# display.net
KiCad netlist of a schematic drawn in Altium Designer
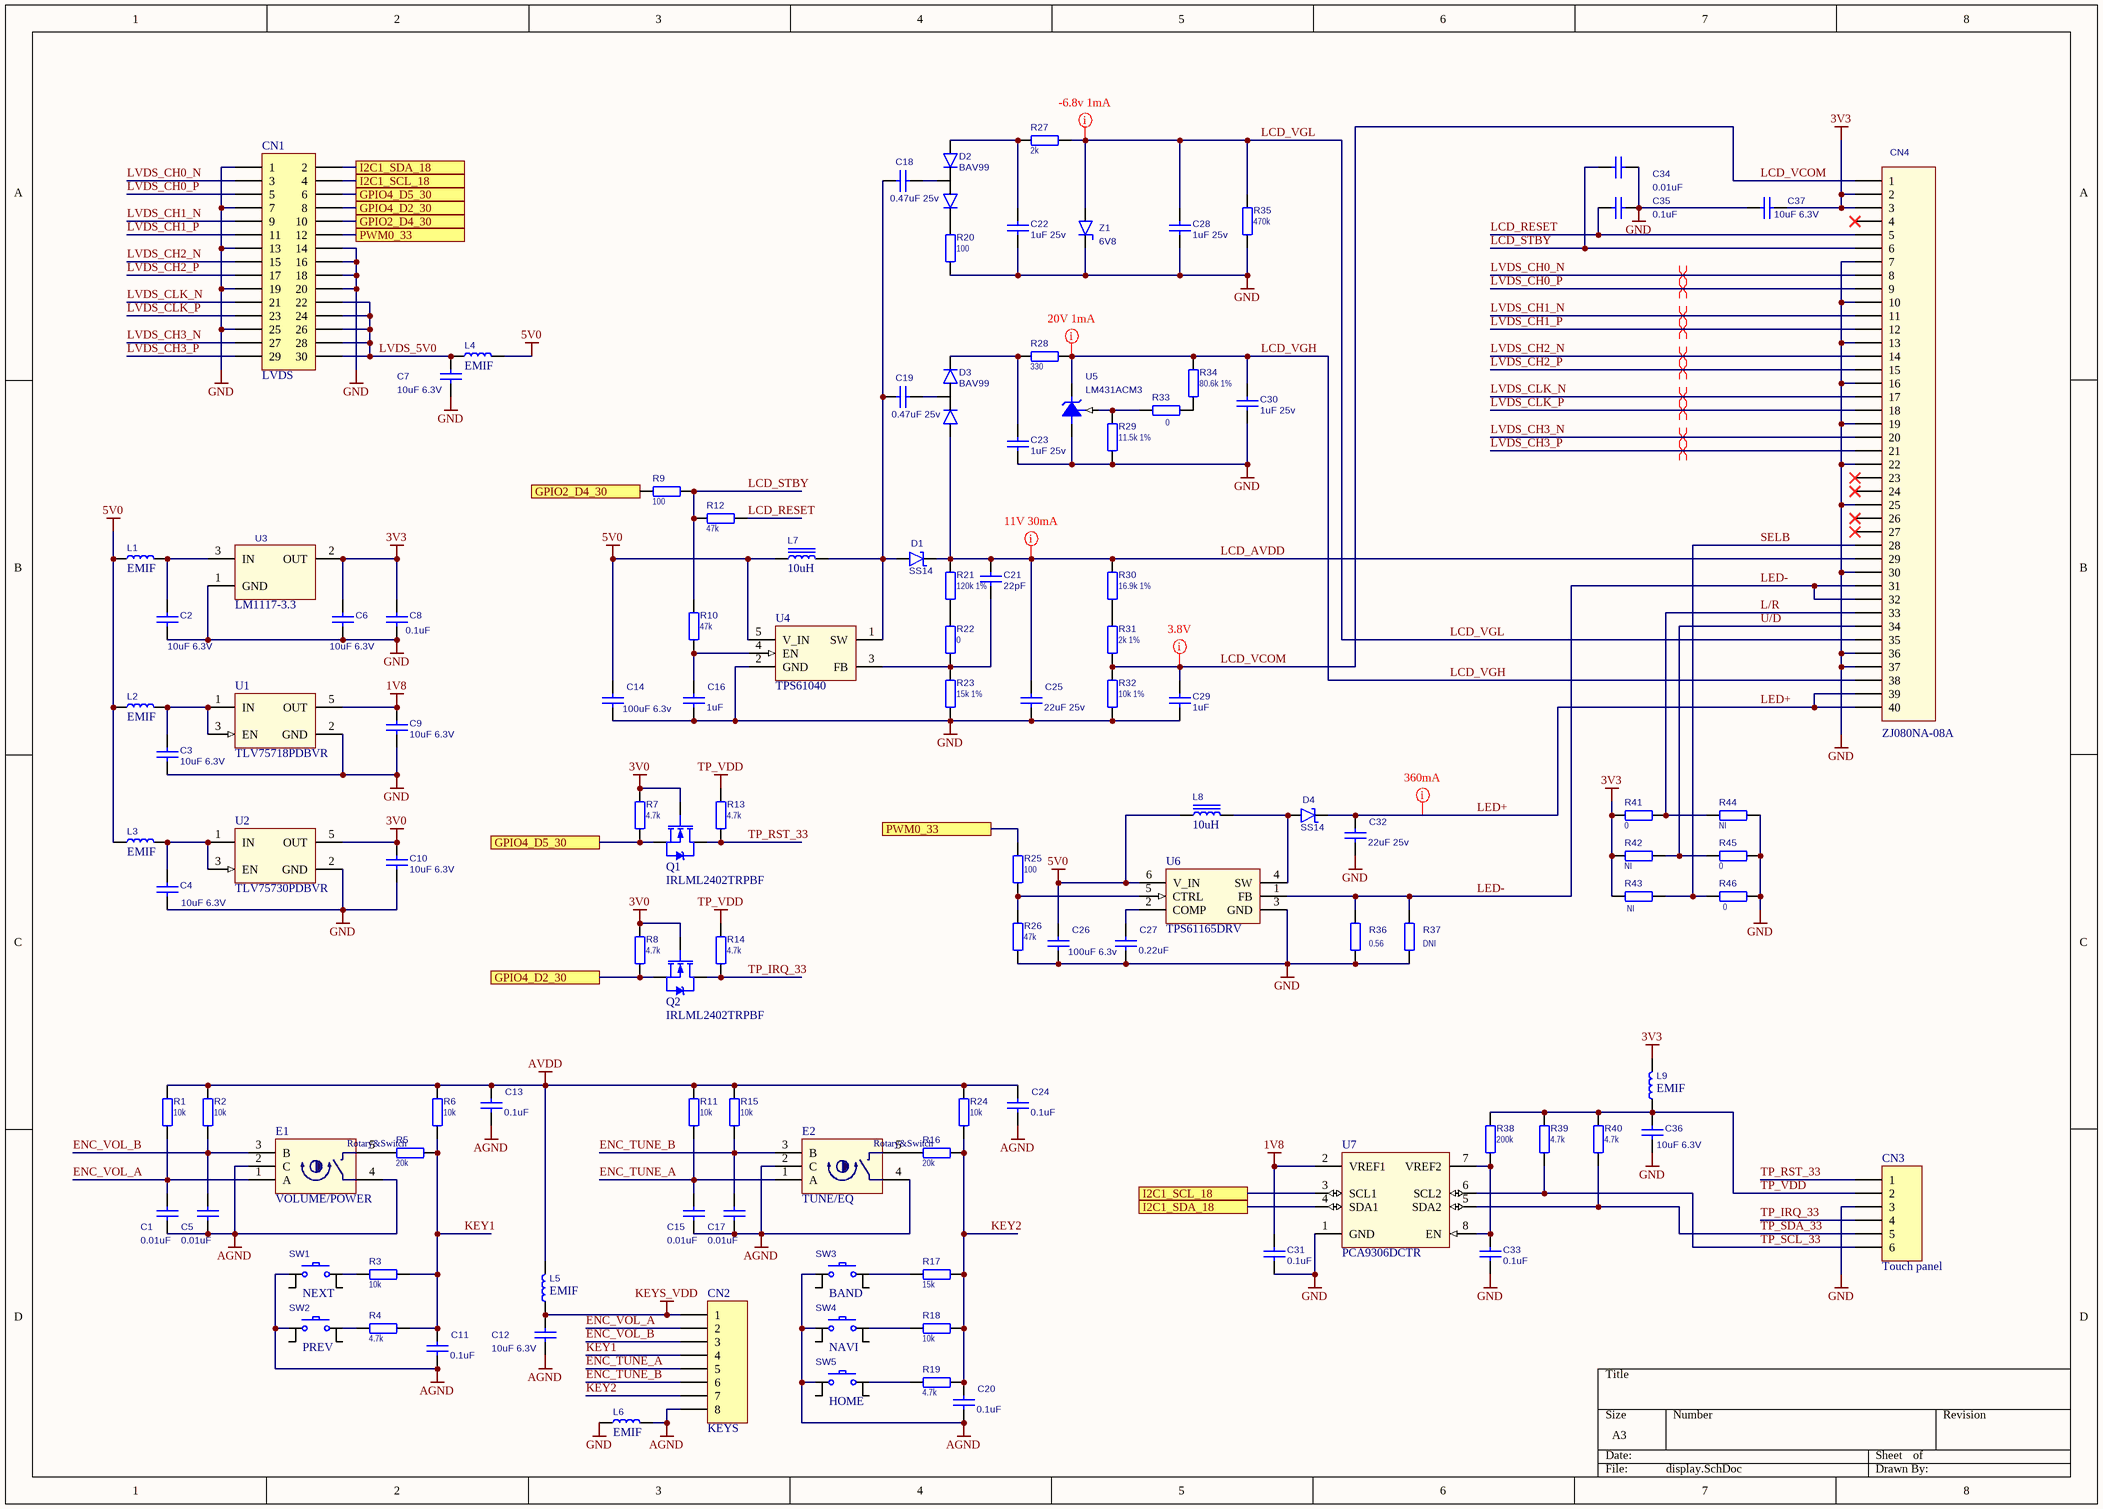
[diagram p0: display.SchDoc]

(export (version "E")
  (design (tool "Eeschema 10.0.6"))
  (components
    (comp (ref "C1")
      (value "0.01uF")
      (footprint "Capacitors:C0603")
      (description "CAP_NPOL")
      (fields (field (name "Comment") "CL10B103KB8NNNC"))
      (libsource (lib "capacitors") (part "CAP_NPOL"))
    )
    (comp (ref "C2")
      (value "10uF 6.3V")
      (footprint "Capacitors:C0603")
      (description "CAP_NPOL")
      (fields (field (name "Comment") "CC0603MRX5R5BB106"))
      (libsource (lib "capacitors") (part "CAP_NPOL"))
    )
    (comp (ref "C3")
      (value "10uF 6.3V")
      (footprint "Capacitors:C0603")
      (description "CAP_NPOL")
      (fields (field (name "Comment") "CC0603MRX5R5BB106"))
      (libsource (lib "capacitors") (part "CAP_NPOL"))
    )
    (comp (ref "C4")
      (value "10uF 6.3V")
      (footprint "Capacitors:C0603")
      (description "CAP_NPOL")
      (fields (field (name "Comment") "CC0603MRX5R5BB106"))
      (libsource (lib "capacitors") (part "CAP_NPOL"))
    )
    (comp (ref "C5")
      (value "0.01uF")
      (footprint "Capacitors:C0603")
      (description "CAP_NPOL")
      (fields (field (name "Comment") "CL10B103KB8NNNC"))
      (libsource (lib "capacitors") (part "CAP_NPOL"))
    )
    (comp (ref "C6")
      (value "10uF 6.3V")
      (footprint "Capacitors:C0603")
      (description "CAP_NPOL")
      (fields (field (name "Comment") "CC0603MRX5R5BB106"))
      (libsource (lib "capacitors") (part "CAP_NPOL"))
    )
    (comp (ref "C7")
      (value "10uF 6.3V")
      (footprint "Capacitors:C0603")
      (description "CAP_NPOL")
      (fields (field (name "Comment") "CC0603MRX5R5BB106"))
      (libsource (lib "capacitors") (part "CAP_NPOL"))
    )
    (comp (ref "C8")
      (value "0.1uF")
      (footprint "C0603")
      (description "CAP_NPOL")
      (fields (field (name "Comment") "C1608X7R1H104K080AA"))
      (libsource (lib "capacitors") (part "CAP_NPOL"))
    )
    (comp (ref "C9")
      (value "10uF 6.3V")
      (footprint "Capacitors:C0603")
      (description "CAP_NPOL")
      (fields (field (name "Comment") "CC0603MRX5R5BB106"))
      (libsource (lib "capacitors") (part "CAP_NPOL"))
    )
    (comp (ref "C10")
      (value "10uF 6.3V")
      (footprint "Capacitors:C0603")
      (description "CAP_NPOL")
      (fields (field (name "Comment") "CC0603MRX5R5BB106"))
      (libsource (lib "capacitors") (part "CAP_NPOL"))
    )
    (comp (ref "C11")
      (value "0.1uF")
      (footprint "Capacitors:C0603")
      (description "CAP_NPOL")
      (fields (field (name "Comment") "C1608X7R1H104K080AA"))
      (libsource (lib "capacitors") (part "CAP_NPOL"))
    )
    (comp (ref "C12")
      (value "10uF 6.3V")
      (footprint "Capacitors:C0603")
      (description "CAP_NPOL")
      (fields (field (name "Comment") "CC0603MRX5R5BB106"))
      (libsource (lib "capacitors") (part "CAP_NPOL"))
    )
    (comp (ref "C13")
      (value "0.1uF")
      (footprint "Capacitors:C0603")
      (description "CAP_NPOL")
      (fields (field (name "Comment") "C1608X7R1H104K080AA"))
      (libsource (lib "capacitors") (part "CAP_NPOL"))
    )
    (comp (ref "C14")
      (value "100uF 6.3v")
      (footprint "C1206")
      (description "CAP_NPOL")
      (fields (field (name "Comment") "CL31A107MQHNNNE"))
      (libsource (lib "capacitors") (part "CAP_NPOL"))
    )
    (comp (ref "C15")
      (value "0.01uF")
      (footprint "Capacitors:C0603")
      (description "CAP_NPOL")
      (fields (field (name "Comment") "CL10B103KB8NNNC"))
      (libsource (lib "capacitors") (part "CAP_NPOL"))
    )
    (comp (ref "C16")
      (value "1uF")
      (footprint "C0603")
      (description "CAP_NPOL")
      (fields (field (name "Comment") "GRM188R71E105KA12D"))
      (libsource (lib "capacitors") (part "CAP_NPOL"))
    )
    (comp (ref "C17")
      (value "0.01uF")
      (footprint "Capacitors:C0603")
      (description "CAP_NPOL")
      (fields (field (name "Comment") "CL10B103KB8NNNC"))
      (libsource (lib "capacitors") (part "CAP_NPOL"))
    )
    (comp (ref "C18")
      (value "0.47uF 25v")
      (footprint "C0603")
      (description "CAP_NPOL")
      (fields (field (name "Comment") "GRM188R71E474KA12D"))
      (libsource (lib "capacitors") (part "CAP_NPOL"))
    )
    (comp (ref "C19")
      (value "0.47uF 25v")
      (footprint "C0603")
      (description "CAP_NPOL")
      (fields (field (name "Comment") "GRM188R71E474KA12D"))
      (libsource (lib "capacitors") (part "CAP_NPOL"))
    )
    (comp (ref "C20")
      (value "0.1uF")
      (footprint "Capacitors:C0603")
      (description "CAP_NPOL")
      (fields (field (name "Comment") "C1608X7R1H104K080AA"))
      (libsource (lib "capacitors") (part "CAP_NPOL"))
    )
    (comp (ref "C21")
      (value "22pF")
      (footprint "C0603")
      (description "CAP_NPOL")
      (fields (field (name "Comment") "CL10C220JB8NNNC"))
      (libsource (lib "capacitors") (part "CAP_NPOL"))
    )
    (comp (ref "C22")
      (value "1uF 25v")
      (footprint "Capacitors:C0805")
      (description "CAP_NPOL")
      (fields (field (name "Comment") "GRM188R71E105KA12D"))
      (libsource (lib "capacitors") (part "CAP_NPOL"))
    )
    (comp (ref "C23")
      (value "1uF 25v")
      (footprint "Capacitors:C0805")
      (description "CAP_NPOL")
      (fields (field (name "Comment") "GRM188R71E105KA12D"))
      (libsource (lib "capacitors") (part "CAP_NPOL"))
    )
    (comp (ref "C24")
      (value "0.1uF")
      (footprint "Capacitors:C0603")
      (description "CAP_NPOL")
      (fields (field (name "Comment") "C1608X7R1H104K080AA"))
      (libsource (lib "capacitors") (part "CAP_NPOL"))
    )
    (comp (ref "C25")
      (value "22uF 25v")
      (footprint "C0805")
      (description "CAP_NPOL")
      (fields (field (name "Comment") "CL21A226MAQNNNE"))
      (libsource (lib "capacitors") (part "CAP_NPOL"))
    )
    (comp (ref "C26")
      (value "100uF 6.3v")
      (footprint "C1206")
      (description "CAP_NPOL")
      (fields (field (name "Comment") "CL31A107MQHNNNE"))
      (libsource (lib "capacitors") (part "CAP_NPOL"))
    )
    (comp (ref "C27")
      (value "0.22uF")
      (footprint "C0603")
      (description "CAP_NPOL")
      (fields (field (name "Comment") "CC0603ZRY5V8BB224"))
      (libsource (lib "capacitors") (part "CAP_NPOL"))
    )
    (comp (ref "C28")
      (value "1uF 25v")
      (footprint "Capacitors:C0805")
      (description "CAP_NPOL")
      (fields (field (name "Comment") "GRM188R71E105KA12D"))
      (libsource (lib "capacitors") (part "CAP_NPOL"))
    )
    (comp (ref "C29")
      (value "1uF")
      (footprint "Capacitors:C0805")
      (description "CAP_NPOL")
      (fields (field (name "Comment") "GRM188R71E105KA12D"))
      (libsource (lib "capacitors") (part "CAP_NPOL"))
    )
    (comp (ref "C30")
      (value "1uF 25v")
      (footprint "Capacitors:C0805")
      (description "CAP_NPOL")
      (fields (field (name "Comment") "GRM188R71E105KA12D"))
      (libsource (lib "capacitors") (part "CAP_NPOL"))
    )
    (comp (ref "C31")
      (value "0.1uF")
      (footprint "Capacitors:C0603")
      (description "CAP_NPOL")
      (fields (field (name "Comment") "C1608X7R1H104K080AA"))
      (libsource (lib "capacitors") (part "CAP_NPOL"))
    )
    (comp (ref "C32")
      (value "22uF 25v")
      (footprint "C0805")
      (description "CAP_NPOL")
      (fields (field (name "Comment") "CL21A226MAQNNNE"))
      (libsource (lib "capacitors") (part "CAP_NPOL"))
    )
    (comp (ref "C33")
      (value "0.1uF")
      (footprint "Capacitors:C0603")
      (description "CAP_NPOL")
      (fields (field (name "Comment") "C1608X7R1H104K080AA"))
      (libsource (lib "capacitors") (part "CAP_NPOL"))
    )
    (comp (ref "C34")
      (value "0.01uF")
      (footprint "C0603")
      (description "CAP_NPOL")
      (fields (field (name "Comment") "CL10B103KB8NNNC"))
      (libsource (lib "capacitors") (part "CAP_NPOL"))
    )
    (comp (ref "C35")
      (value "0.1uF")
      (footprint "C0603")
      (description "CAP_NPOL")
      (fields (field (name "Comment") "C1608X7R1H104K080AA"))
      (libsource (lib "capacitors") (part "CAP_NPOL"))
    )
    (comp (ref "C36")
      (value "10uF 6.3V")
      (footprint "Capacitors:C0603")
      (description "CAP_NPOL")
      (fields (field (name "Comment") "CC0603MRX5R5BB106"))
      (libsource (lib "capacitors") (part "CAP_NPOL"))
    )
    (comp (ref "C37")
      (value "10uF 6.3V")
      (footprint "Capacitors:C0603")
      (description "CAP_NPOL")
      (fields (field (name "Comment") "CC0603MRX5R5BB106"))
      (libsource (lib "capacitors") (part "CAP_NPOL"))
    )
    (comp (ref "CN1")
      (value "LVDS")
      (footprint "DF13EA-30DP-1.25V")
      (description "Header, 15-Pin, Dual row")
      (fields (field (name "PUBLISHER") "Altium Limited"))
      (libsource (lib "HDR") (part "HDR 15X2"))
    )
    (comp (ref "CN2")
      (value "KEYS")
      (footprint "1.25-8AW")
      (description "Header, 8-Pin")
      (fields (field (name "PUBLISHER") "Altium Limited"))
      (libsource (lib "HDR") (part "HDR 8"))
    )
    (comp (ref "CN3")
      (value "Touch panel")
      (footprint "6S-0.5SH")
      (description "Header, 6-Pin")
      (fields (field (name "PUBLISHER") "Altium Limited"))
      (libsource (lib "Miscellaneous Connectors") (part "Header 6"))
    )
    (comp (ref "CN4")
      (value "ZJ080NA-08A")
      (footprint "40S-0.5SH")
      (description "DT38")
      (fields (field (name "Comment") "FH12-40"))
      (libsource (lib "FPC_FH12-40S-0.5SH") (part "FH12-40"))
    )
    (comp (ref "D1")
      (value "SS14")
      (footprint "SMA")
      (description "SHOTTKY")
      (libsource (lib "diodes") (part "SHOTTKY"))
    )
    (comp (ref "D2")
      (value "BAV99")
      (footprint "SOT-23-3")
      (description "Dual series 1")
      (fields (field (name "Comment") "BAV99.215"))
      (libsource (lib "diodes") (part "DIODE_DUAL_1"))
    )
    (comp (ref "D3")
      (value "BAV99")
      (footprint "SOT-23-3")
      (description "Dual series 1")
      (fields (field (name "Comment") "BAV99.215"))
      (libsource (lib "diodes") (part "DIODE_DUAL_1"))
    )
    (comp (ref "D4")
      (value "SS14")
      (footprint "SMA")
      (description "SHOTTKY")
      (fields (field (name "Comment") "SS24"))
      (libsource (lib "diodes") (part "SHOTTKY"))
    )
    (comp (ref "E1")
      (value "VOLUME/POWER")
      (footprint "Rotary Encoder")
      (description "ENC_SW")
      (libsource (lib "encoders") (part "ENC_SW"))
    )
    (comp (ref "E2")
      (value "TUNE/EQ")
      (footprint "Rotary Encoder")
      (description "ENC_SW")
      (libsource (lib "encoders") (part "ENC_SW"))
    )
    (comp (ref "L1")
      (value "EMIF")
      (footprint "IND0805")
      (description "IND_WO_IRON")
      (fields (field (name "Comment") "BLM21PG221SN1D"))
      (libsource (lib "inductors") (part "IND_WO_IRON"))
    )
    (comp (ref "L2")
      (value "EMIF")
      (footprint "IND0603")
      (description "IND_WO_IRON")
      (fields (field (name "Comment") "BLM18AG102SN1D"))
      (libsource (lib "inductors") (part "IND_WO_IRON"))
    )
    (comp (ref "L3")
      (value "EMIF")
      (footprint "IND0603")
      (description "IND_WO_IRON")
      (fields (field (name "Comment") "BLM18AG102SN1D"))
      (libsource (lib "inductors") (part "IND_WO_IRON"))
    )
    (comp (ref "L4")
      (value "EMIF")
      (footprint "IND0805")
      (description "IND_WO_IRON")
      (fields (field (name "Comment") "BLM21PG221SN1D"))
      (libsource (lib "") (part "IND_WO_IRON_1"))
    )
    (comp (ref "L5")
      (value "EMIF")
      (footprint "IND0603")
      (description "IND_WO_IRON")
      (fields (field (name "Comment") "BLM18AG102SN1D"))
      (libsource (lib "") (part "IND_WO_IRON_1"))
    )
    (comp (ref "L6")
      (value "EMIF")
      (footprint "IND0603")
      (description "IND_WO_IRON")
      (fields (field (name "Comment") "BLM18AG102SN1D"))
      (libsource (lib "") (part "IND_WO_IRON_1"))
    )
    (comp (ref "L7")
      (value "10uH")
      (footprint "CDRH3D16")
      (description "IND_W_IRON")
      (fields (field (name "Comment") "CDRH3D16NP-100NC"))
      (libsource (lib "inductors") (part "IND_W_IRON"))
    )
    (comp (ref "L8")
      (value "10uH")
      (footprint "CDRH6D28")
      (description "IND_W_IRON")
      (fields (field (name "Comment") "CDRH6D28-100NC"))
      (libsource (lib "inductors") (part "IND_W_IRON"))
    )
    (comp (ref "L9")
      (value "EMIF")
      (footprint "IND0603")
      (description "IND_WO_IRON")
      (fields (field (name "Comment") "BLM18AG102SN1D"))
      (libsource (lib "inductors") (part "IND_WO_IRON"))
    )
    (comp (ref "Q1")
      (value "IRLML2402TRPBF")
      (footprint "SOT-23-3")
      (description "HEXFET Power MOSFET")
      (libsource (lib "MOSFET") (part "N-Channel"))
    )
    (comp (ref "Q2")
      (value "IRLML2402TRPBF")
      (footprint "SOT-23-3")
      (description "HEXFET Power MOSFET")
      (libsource (lib "MOSFET") (part "N-Channel"))
    )
    (comp (ref "R1")
      (value "10k")
      (footprint "R0603")
      (description "RES")
      (libsource (lib "resistors") (part "RESISTOR"))
    )
    (comp (ref "R2")
      (value "10k")
      (footprint "R0603")
      (description "RES")
      (libsource (lib "resistors") (part "RESISTOR"))
    )
    (comp (ref "R3")
      (value "10k")
      (footprint "R0603")
      (description "RES")
      (libsource (lib "resistors") (part "RESISTOR"))
    )
    (comp (ref "R4")
      (value "4.7k")
      (footprint "R0603")
      (description "RES")
      (libsource (lib "resistors") (part "RESISTOR"))
    )
    (comp (ref "R5")
      (value "20k")
      (footprint "R0603")
      (description "RES")
      (libsource (lib "resistors") (part "RESISTOR"))
    )
    (comp (ref "R6")
      (value "10k")
      (footprint "R0603")
      (description "RES")
      (libsource (lib "resistors") (part "RESISTOR"))
    )
    (comp (ref "R7")
      (value "4.7k")
      (footprint "R0603")
      (description "RES")
      (libsource (lib "resistors") (part "RESISTOR"))
    )
    (comp (ref "R8")
      (value "4.7k")
      (footprint "R0603")
      (description "RES")
      (libsource (lib "resistors") (part "RESISTOR"))
    )
    (comp (ref "R9") (value "100") (footprint "R0603") (libsource (lib "resistors") (part "RESISTOR")))
    (comp (ref "R10")
      (value "47k")
      (footprint "R0603")
      (description "RES")
      (libsource (lib "resistors") (part "RESISTOR"))
    )
    (comp (ref "R11")
      (value "10k")
      (footprint "R0603")
      (description "RES")
      (libsource (lib "resistors") (part "RESISTOR"))
    )
    (comp (ref "R12")
      (value "47k")
      (footprint "R0603")
      (description "RES")
      (libsource (lib "resistors") (part "RESISTOR"))
    )
    (comp (ref "R13")
      (value "4.7k")
      (footprint "R0603")
      (description "RES")
      (libsource (lib "resistors") (part "RESISTOR"))
    )
    (comp (ref "R14")
      (value "4.7k")
      (footprint "R0603")
      (description "RES")
      (libsource (lib "resistors") (part "RESISTOR"))
    )
    (comp (ref "R15")
      (value "10k")
      (footprint "R0603")
      (description "RES")
      (libsource (lib "resistors") (part "RESISTOR"))
    )
    (comp (ref "R16")
      (value "20k")
      (footprint "R0603")
      (description "RES")
      (libsource (lib "resistors") (part "RESISTOR"))
    )
    (comp (ref "R17")
      (value "15k")
      (footprint "R0603")
      (description "RES")
      (libsource (lib "resistors") (part "RESISTOR"))
    )
    (comp (ref "R18")
      (value "10k")
      (footprint "R0603")
      (description "RES")
      (libsource (lib "resistors") (part "RESISTOR"))
    )
    (comp (ref "R19")
      (value "4.7k")
      (footprint "R0603")
      (description "RES")
      (libsource (lib "resistors") (part "RESISTOR"))
    )
    (comp (ref "R20")
      (value "100")
      (footprint "R0603")
      (description "RES")
      (libsource (lib "resistors") (part "RESISTOR"))
    )
    (comp (ref "R21")
      (value "120k 1%")
      (footprint "R0603")
      (description "RES")
      (fields (field (name "Comment") "120k"))
      (libsource (lib "resistors") (part "RESISTOR"))
    )
    (comp (ref "R22")
      (value "0")
      (footprint "R0603")
      (description "RES")
      (libsource (lib "resistors") (part "RESISTOR"))
    )
    (comp (ref "R23")
      (value "15k 1%")
      (footprint "R0603")
      (description "RES")
      (fields (field (name "Comment") "15k"))
      (libsource (lib "resistors") (part "RESISTOR"))
    )
    (comp (ref "R24")
      (value "10k")
      (footprint "R0603")
      (description "RES")
      (libsource (lib "resistors") (part "RESISTOR"))
    )
    (comp (ref "R25") (value "100") (footprint "R0603") (libsource (lib "resistors") (part "RESISTOR")))
    (comp (ref "R26")
      (value "47k")
      (footprint "R0603")
      (description "RES")
      (libsource (lib "resistors") (part "RESISTOR"))
    )
    (comp (ref "R27")
      (value "2k")
      (footprint "R0603")
      (description "RES")
      (libsource (lib "resistors") (part "RESISTOR"))
    )
    (comp (ref "R28")
      (value "330")
      (footprint "R0805")
      (description "RES")
      (libsource (lib "resistors") (part "RESISTOR"))
    )
    (comp (ref "R29")
      (value "11.5k 1%")
      (footprint "R0603")
      (description "RES")
      (fields (field (name "Comment") "11.5k"))
      (libsource (lib "resistors") (part "RESISTOR"))
    )
    (comp (ref "R30")
      (value "16.9k 1%")
      (footprint "R0805")
      (description "RES")
      (fields (field (name "Comment") "16.9k"))
      (libsource (lib "resistors") (part "RESISTOR"))
    )
    (comp (ref "R31")
      (value "2k 1%")
      (footprint "R0603")
      (description "RES")
      (fields (field (name "Comment") "2k"))
      (libsource (lib "resistors") (part "RESISTOR"))
    )
    (comp (ref "R32")
      (value "10k 1%")
      (footprint "R0603")
      (description "RES")
      (fields (field (name "Comment") "10k"))
      (libsource (lib "resistors") (part "RESISTOR"))
    )
    (comp (ref "R33")
      (value "0")
      (footprint "R0603")
      (description "RES")
      (libsource (lib "resistors") (part "RESISTOR"))
    )
    (comp (ref "R34")
      (value "80.6k 1%")
      (footprint "R0603")
      (description "RES")
      (fields (field (name "Comment") "80.6k"))
      (libsource (lib "resistors") (part "RESISTOR"))
    )
    (comp (ref "R35")
      (value "470k")
      (footprint "R0603")
      (description "RES")
      (libsource (lib "resistors") (part "RESISTOR"))
    )
    (comp (ref "R36")
      (value "0.56")
      (footprint "R0805")
      (description "RES")
      (libsource (lib "resistors") (part "RESISTOR"))
    )
    (comp (ref "R37")
      (value "DNI")
      (footprint "R0805")
      (description "RES")
      (libsource (lib "resistors") (part "RESISTOR"))
    )
    (comp (ref "R38")
      (value "200k")
      (footprint "R0603")
      (description "RES")
      (libsource (lib "resistors") (part "RESISTOR"))
    )
    (comp (ref "R39")
      (value "4.7k")
      (footprint "R0603")
      (description "RES")
      (libsource (lib "resistors") (part "RESISTOR"))
    )
    (comp (ref "R40")
      (value "4.7k")
      (footprint "R0603")
      (description "RES")
      (libsource (lib "resistors") (part "RESISTOR"))
    )
    (comp (ref "R41")
      (value "0")
      (footprint "R0603")
      (description "RES")
      (libsource (lib "resistors") (part "RESISTOR"))
    )
    (comp (ref "R42")
      (value "NI")
      (footprint "R0603")
      (description "RES")
      (fields (field (name "Comment") "DNI"))
      (libsource (lib "resistors") (part "RESISTOR"))
    )
    (comp (ref "R43")
      (value "NI")
      (footprint "R0603")
      (description "RES")
      (fields (field (name "Comment") "DNI"))
      (libsource (lib "resistors") (part "RESISTOR"))
    )
    (comp (ref "R44")
      (value "NI")
      (footprint "R0603")
      (description "RES")
      (fields (field (name "Comment") "DNI"))
      (libsource (lib "resistors") (part "RESISTOR"))
    )
    (comp (ref "R45")
      (value "0")
      (footprint "R0603")
      (description "RES")
      (libsource (lib "resistors") (part "RESISTOR"))
    )
    (comp (ref "R46")
      (value "0")
      (footprint "R0603")
      (description "RES")
      (libsource (lib "resistors") (part "RESISTOR"))
    )
    (comp (ref "SW1")
      (value "NEXT")
      (footprint "12X12-SMT")
      (libsource (lib "SW-TACT-4PIN") (part "SW-TACT-4PIN"))
    )
    (comp (ref "SW2")
      (value "PREV")
      (footprint "12X12-SMT")
      (libsource (lib "SW-TACT-4PIN") (part "SW-TACT-4PIN"))
    )
    (comp (ref "SW3")
      (value "BAND")
      (footprint "12X12-SMT")
      (libsource (lib "SW-TACT-4PIN") (part "SW-TACT-4PIN"))
    )
    (comp (ref "SW4")
      (value "NAVI")
      (footprint "12X12-SMT")
      (libsource (lib "SW-TACT-4PIN") (part "SW-TACT-4PIN"))
    )
    (comp (ref "SW5")
      (value "HOME")
      (footprint "12X12-SMT")
      (libsource (lib "SW-TACT-4PIN") (part "SW-TACT-4PIN"))
    )
    (comp (ref "U1")
      (value "TLV75718PDBVR")
      (footprint "SOT-23-5")
      (description "Capacitor-Free, 300-mA, Low-Dropout Regulator with Foldback Current Limit for Portable Devices")
      (libsource (lib "TLV733P") (part "TLV733P"))
    )
    (comp (ref "U2")
      (value "TLV75730PDBVR")
      (footprint "SOT-23-5")
      (description "Capacitor-Free, 300-mA, Low-Dropout Regulator with Foldback Current Limit for Portable Devices")
      (libsource (lib "TLV733P") (part "TLV733P"))
    )
    (comp (ref "U3")
      (value "LM1117-3.3")
      (footprint "SOT-223")
      (description "LM1117")
      (libsource (lib "LM1117") (part "LM1117"))
    )
    (comp (ref "U4") (value "TPS61040") (footprint "SOT-23-5") (libsource (lib "TPS6104x") (part "TPS6104x")))
    (comp (ref "U5")
      (value "LM431ACM3")
      (footprint "SOT-23-3")
      (description "Adjustable Precision Zener Shunt Regulator, 3-pin SOT-23")
      (fields
        (field (name "MANUFACTURER") "National Semiconductor")
        (field (name "PUBLISHER") "Altium Limited")
      )
      (libsource (lib "NSC MiscPower") (part "LM431ACM3"))
    )
    (comp (ref "U6")
      (value "TPS61165DRV")
      (footprint "SOT-23-6")
      (description "TPS61165DRV (WSON6 package)")
      (fields (field (name "Comment") "TPS61165"))
      (libsource (lib "TPS61165") (part "TPS61165DRV"))
    )
    (comp (ref "U7")
      (value "PCA9306DCTR")
      (footprint "PSOP:PSOP-8")
      (description "PCA9306 Dual Bidirectional I2C Bus and SMBus Voltage-Level Translator")
      (libsource (lib "PCA9306") (part "PCA9306"))
    )
    (comp (ref "Z1")
      (value "6V8")
      (footprint "SOD-80C")
      (description "ZENNER")
      (fields (field (name "Comment") "BZV55-C6V8"))
      (libsource (lib "diodes") (part "ZENNER"))
    )
  )
  (nets
    (net (code "1") (name "/ENC_TUNE_A") (class "Default")
      (node (ref "C15") (pin "2") (pinfunction "2_2") (pintype "passive"))
      (node (ref "CN2") (pin "5") (pinfunction "5_5") (pintype "passive"))
      (node (ref "E2") (pin "1") (pinfunction "A_1") (pintype "passive"))
      (node (ref "R11") (pin "1") (pinfunction "1_1") (pintype "passive"))
    )
    (net (code "2") (name "/ENC_TUNE_B") (class "Default")
      (node (ref "C17") (pin "2") (pinfunction "2_2") (pintype "passive"))
      (node (ref "CN2") (pin "6") (pinfunction "6_6") (pintype "passive"))
      (node (ref "E2") (pin "3") (pinfunction "B_3") (pintype "passive"))
      (node (ref "R15") (pin "2") (pinfunction "2_2") (pintype "passive"))
    )
    (net (code "3") (name "/ENC_VOL_A") (class "Default")
      (node (ref "C1") (pin "2") (pinfunction "2_2") (pintype "passive"))
      (node (ref "CN2") (pin "2") (pinfunction "2_2") (pintype "passive"))
      (node (ref "E1") (pin "1") (pinfunction "A_1") (pintype "passive"))
      (node (ref "R1") (pin "1") (pinfunction "1_1") (pintype "passive"))
    )
    (net (code "4") (name "/ENC_VOL_B") (class "Default")
      (node (ref "C5") (pin "2") (pinfunction "2_2") (pintype "passive"))
      (node (ref "CN2") (pin "3") (pinfunction "3_3") (pintype "passive"))
      (node (ref "E1") (pin "3") (pinfunction "B_3") (pintype "passive"))
      (node (ref "R2") (pin "2") (pinfunction "2_2") (pintype "passive"))
    )
    (net (code "5") (name "/GPIO2_D4_30") (class "Default")
      (node (ref "CN1") (pin "10") (pinfunction "10_10") (pintype "passive"))
      (node (ref "R9") (pin "2") (pinfunction "2_2") (pintype "passive"))
    )
    (net (code "6") (name "/GPIO4_D2_30") (class "Default")
      (node (ref "CN1") (pin "8") (pinfunction "8_8") (pintype "passive"))
      (node (ref "Q2") (pin "2") (pinfunction "S_2") (pintype "passive"))
      (node (ref "R8") (pin "1") (pinfunction "1_1") (pintype "passive"))
    )
    (net (code "7") (name "/GPIO4_D5_30") (class "Default")
      (node (ref "CN1") (pin "6") (pinfunction "6_6") (pintype "passive"))
      (node (ref "Q1") (pin "2") (pinfunction "S_2") (pintype "passive"))
      (node (ref "R7") (pin "1") (pinfunction "1_1") (pintype "passive"))
    )
    (net (code "8") (name "/I2C1_SCL_18") (class "Default")
      (node (ref "CN1") (pin "4") (pinfunction "4_4") (pintype "passive"))
      (node (ref "U7") (pin "3") (pinfunction "SCL1_3") (pintype "bidirectional"))
    )
    (net (code "9") (name "/I2C1_SDA_18") (class "Default")
      (node (ref "CN1") (pin "2") (pinfunction "2_2") (pintype "passive"))
      (node (ref "U7") (pin "4") (pinfunction "SDA1_4") (pintype "bidirectional"))
    )
    (net (code "10") (name "/KEY1") (class "Default")
      (node (ref "C11") (pin "1") (pinfunction "1_1") (pintype "passive"))
      (node (ref "CN2") (pin "4") (pinfunction "4_4") (pintype "passive"))
      (node (ref "R3") (pin "2") (pinfunction "2_2") (pintype "passive"))
      (node (ref "R4") (pin "2") (pinfunction "2_2") (pintype "passive"))
      (node (ref "R5") (pin "1") (pinfunction "1_1") (pintype "passive"))
      (node (ref "R6") (pin "1") (pinfunction "1_1") (pintype "passive"))
    )
    (net (code "11") (name "/KEY2") (class "Default")
      (node (ref "C20") (pin "1") (pinfunction "1_1") (pintype "passive"))
      (node (ref "CN2") (pin "7") (pinfunction "7_7") (pintype "passive"))
      (node (ref "R16") (pin "1") (pinfunction "1_1") (pintype "passive"))
      (node (ref "R17") (pin "2") (pinfunction "2_2") (pintype "passive"))
      (node (ref "R18") (pin "2") (pinfunction "2_2") (pintype "passive"))
      (node (ref "R19") (pin "2") (pinfunction "2_2") (pintype "passive"))
      (node (ref "R24") (pin "1") (pinfunction "1_1") (pintype "passive"))
    )
    (net (code "12") (name "/LCD_AVDD") (class "Default")
      (node (ref "C21") (pin "1") (pinfunction "1_1") (pintype "passive"))
      (node (ref "C25") (pin "2") (pinfunction "2_2") (pintype "passive"))
      (node (ref "CN4") (pin "29") (pinfunction "29_29") (pintype "passive"))
      (node (ref "D1") (pin "2") (pinfunction "K_2") (pintype "passive"))
      (node (ref "D3") (pin "1") (pinfunction "A_1") (pintype "passive"))
      (node (ref "R21") (pin "2") (pinfunction "2_2") (pintype "passive"))
      (node (ref "R30") (pin "2") (pinfunction "2_2") (pintype "passive"))
    )
    (net (code "13") (name "/LCD_RESET") (class "Default")
      (node (ref "C35") (pin "2") (pinfunction "2_2") (pintype "passive"))
      (node (ref "CN4") (pin "5") (pinfunction "5_5") (pintype "passive"))
      (node (ref "R12") (pin "1") (pinfunction "1_1") (pintype "passive"))
    )
    (net (code "14") (name "/LCD_STBY") (class "Default")
      (node (ref "C34") (pin "2") (pinfunction "2_2") (pintype "passive"))
      (node (ref "CN4") (pin "6") (pinfunction "6_6") (pintype "passive"))
      (node (ref "R10") (pin "2") (pinfunction "2_2") (pintype "passive"))
      (node (ref "R12") (pin "2") (pinfunction "2_2") (pintype "passive"))
      (node (ref "R9") (pin "1") (pinfunction "1_1") (pintype "passive"))
    )
    (net (code "15") (name "/LCD_VCOM") (class "Default")
      (node (ref "C29") (pin "2") (pinfunction "2_2") (pintype "passive"))
      (node (ref "CN4") (pin "1") (pinfunction "1_1") (pintype "passive"))
      (node (ref "R31") (pin "1") (pinfunction "1_1") (pintype "passive"))
      (node (ref "R32") (pin "2") (pinfunction "2_2") (pintype "passive"))
    )
    (net (code "16") (name "/LCD_VGH") (class "Default")
      (node (ref "C30") (pin "2") (pinfunction "2_2") (pintype "passive"))
      (node (ref "CN4") (pin "38") (pinfunction "38_38") (pintype "passive"))
      (node (ref "R28") (pin "2") (pinfunction "2_2") (pintype "passive"))
      (node (ref "R34") (pin "2") (pinfunction "2_2") (pintype "passive"))
      (node (ref "U5") (pin "1") (pinfunction "K_1") (pintype "passive"))
    )
    (net (code "17") (name "/LCD_VGL") (class "Default")
      (node (ref "C28") (pin "2") (pinfunction "2_2") (pintype "passive"))
      (node (ref "CN4") (pin "35") (pinfunction "35_35") (pintype "passive"))
      (node (ref "R27") (pin "2") (pinfunction "2_2") (pintype "passive"))
      (node (ref "R35") (pin "2") (pinfunction "2_2") (pintype "passive"))
      (node (ref "Z1") (pin "1") (pinfunction "A_1") (pintype "passive"))
    )
    (net (code "18") (name "/LED+") (class "Default")
      (node (ref "C32") (pin "2") (pinfunction "2_2") (pintype "passive"))
      (node (ref "CN4") (pin "39") (pinfunction "39_39") (pintype "passive"))
      (node (ref "CN4") (pin "40") (pinfunction "40_40") (pintype "passive"))
      (node (ref "D4") (pin "2") (pinfunction "K_2") (pintype "passive"))
    )
    (net (code "19") (name "/LED-") (class "Default")
      (node (ref "CN4") (pin "31") (pinfunction "31_31") (pintype "passive"))
      (node (ref "CN4") (pin "32") (pinfunction "32_32") (pintype "passive"))
      (node (ref "R36") (pin "2") (pinfunction "2_2") (pintype "passive"))
      (node (ref "R37") (pin "2") (pinfunction "2_2") (pintype "passive"))
      (node (ref "U6") (pin "1") (pinfunction "FB_1") (pintype "passive"))
    )
    (net (code "20") (name "/LVDS_5V0") (class "Default")
      (node (ref "C7") (pin "1") (pinfunction "1_1") (pintype "passive"))
      (node (ref "CN1") (pin "22") (pinfunction "22_22") (pintype "passive"))
      (node (ref "CN1") (pin "24") (pinfunction "24_24") (pintype "passive"))
      (node (ref "CN1") (pin "26") (pinfunction "26_26") (pintype "passive"))
      (node (ref "CN1") (pin "28") (pinfunction "28_28") (pintype "passive"))
      (node (ref "CN1") (pin "30") (pinfunction "30_30") (pintype "passive"))
      (node (ref "L4") (pin "2") (pintype "passive"))
    )
    (net (code "21") (name "/LVDS_CH0_N") (class "Default")
      (node (ref "CN1") (pin "3") (pinfunction "3_3") (pintype "passive"))
      (node (ref "CN4") (pin "8") (pinfunction "8_8") (pintype "passive"))
    )
    (net (code "22") (name "/LVDS_CH0_P") (class "Default")
      (node (ref "CN1") (pin "5") (pinfunction "5_5") (pintype "passive"))
      (node (ref "CN4") (pin "9") (pinfunction "9_9") (pintype "passive"))
    )
    (net (code "23") (name "/LVDS_CH1_N") (class "Default")
      (node (ref "CN1") (pin "9") (pinfunction "9_9") (pintype "passive"))
      (node (ref "CN4") (pin "11") (pinfunction "11_11") (pintype "passive"))
    )
    (net (code "24") (name "/LVDS_CH1_P") (class "Default")
      (node (ref "CN1") (pin "11") (pinfunction "11_11") (pintype "passive"))
      (node (ref "CN4") (pin "12") (pinfunction "12_12") (pintype "passive"))
    )
    (net (code "25") (name "/LVDS_CH2_N") (class "Default")
      (node (ref "CN1") (pin "15") (pinfunction "15_15") (pintype "passive"))
      (node (ref "CN4") (pin "14") (pinfunction "14_14") (pintype "passive"))
    )
    (net (code "26") (name "/LVDS_CH2_P") (class "Default")
      (node (ref "CN1") (pin "17") (pinfunction "17_17") (pintype "passive"))
      (node (ref "CN4") (pin "15") (pinfunction "15_15") (pintype "passive"))
    )
    (net (code "27") (name "/LVDS_CH3_N") (class "Default")
      (node (ref "CN1") (pin "27") (pinfunction "27_27") (pintype "passive"))
      (node (ref "CN4") (pin "20") (pinfunction "20_20") (pintype "passive"))
    )
    (net (code "28") (name "/LVDS_CH3_P") (class "Default")
      (node (ref "CN1") (pin "29") (pinfunction "29_29") (pintype "passive"))
      (node (ref "CN4") (pin "21") (pinfunction "21_21") (pintype "passive"))
    )
    (net (code "29") (name "/LVDS_CLK_N") (class "Default")
      (node (ref "CN1") (pin "21") (pinfunction "21_21") (pintype "passive"))
      (node (ref "CN4") (pin "17") (pinfunction "17_17") (pintype "passive"))
    )
    (net (code "30") (name "/LVDS_CLK_P") (class "Default")
      (node (ref "CN1") (pin "23") (pinfunction "23_23") (pintype "passive"))
      (node (ref "CN4") (pin "18") (pinfunction "18_18") (pintype "passive"))
    )
    (net (code "31") (name "/L{slash}R") (class "Default")
      (node (ref "CN4") (pin "33") (pinfunction "33_33") (pintype "passive"))
      (node (ref "R41") (pin "2") (pinfunction "2_2") (pintype "passive"))
      (node (ref "R44") (pin "1") (pinfunction "1_1") (pintype "passive"))
    )
    (net (code "32") (name "/PWM0_33") (class "Default")
      (node (ref "CN1") (pin "12") (pinfunction "12_12") (pintype "passive"))
      (node (ref "R25") (pin "2") (pinfunction "2_2") (pintype "passive"))
    )
    (net (code "33") (name "/SELB") (class "Default")
      (node (ref "CN4") (pin "28") (pinfunction "28_28") (pintype "passive"))
      (node (ref "R43") (pin "2") (pinfunction "2_2") (pintype "passive"))
      (node (ref "R46") (pin "1") (pinfunction "1_1") (pintype "passive"))
    )
    (net (code "34") (name "/TP_IRQ_33") (class "Default")
      (node (ref "CN3") (pin "4") (pinfunction "4_4") (pintype "passive"))
      (node (ref "Q2") (pin "3") (pinfunction "D_3") (pintype "passive"))
      (node (ref "R14") (pin "1") (pinfunction "1_1") (pintype "passive"))
    )
    (net (code "35") (name "/TP_RST_33") (class "Default")
      (node (ref "CN3") (pin "1") (pinfunction "1_1") (pintype "passive"))
      (node (ref "Q1") (pin "3") (pinfunction "D_3") (pintype "passive"))
      (node (ref "R13") (pin "1") (pinfunction "1_1") (pintype "passive"))
    )
    (net (code "36") (name "/TP_SCL_33") (class "Default")
      (node (ref "CN3") (pin "6") (pinfunction "6_6") (pintype "passive"))
      (node (ref "R39") (pin "2") (pinfunction "2_2") (pintype "passive"))
      (node (ref "U7") (pin "6") (pinfunction "SCL2_6") (pintype "bidirectional"))
    )
    (net (code "37") (name "/TP_SDA_33") (class "Default")
      (node (ref "CN3") (pin "5") (pinfunction "5_5") (pintype "passive"))
      (node (ref "R40") (pin "2") (pinfunction "2_2") (pintype "passive"))
      (node (ref "U7") (pin "5") (pinfunction "SDA2_5") (pintype "bidirectional"))
    )
    (net (code "38") (name "/U{slash}D") (class "Default")
      (node (ref "CN4") (pin "34") (pinfunction "34_34") (pintype "passive"))
      (node (ref "R42") (pin "2") (pinfunction "2_2") (pintype "passive"))
      (node (ref "R45") (pin "1") (pinfunction "1_1") (pintype "passive"))
    )
    (net (code "39") (name "1V8") (class "Default")
      (node (ref "C31") (pin "1") (pinfunction "1_1") (pintype "passive"))
      (node (ref "C9") (pin "1") (pinfunction "1_1") (pintype "passive"))
      (node (ref "U1") (pin "5") (pinfunction "OUT_5") (pintype "power_in"))
      (node (ref "U7") (pin "2") (pinfunction "VREF1_2") (pintype "power_in"))
    )
    (net (code "40") (name "3V0") (class "Default")
      (node (ref "C10") (pin "1") (pinfunction "1_1") (pintype "passive"))
      (node (ref "Q1") (pin "1") (pinfunction "G_1") (pintype "passive"))
      (node (ref "Q2") (pin "1") (pinfunction "G_1") (pintype "passive"))
      (node (ref "R7") (pin "2") (pinfunction "2_2") (pintype "passive"))
      (node (ref "R8") (pin "2") (pinfunction "2_2") (pintype "passive"))
      (node (ref "U2") (pin "5") (pinfunction "OUT_5") (pintype "power_in"))
    )
    (net (code "41") (name "3V3") (class "Default")
      (node (ref "C37") (pin "2") (pinfunction "2_2") (pintype "passive"))
      (node (ref "C6") (pin "1") (pinfunction "1_1") (pintype "passive"))
      (node (ref "C8") (pin "2") (pinfunction "2_2") (pintype "passive"))
      (node (ref "CN4") (pin "2") (pinfunction "2_2") (pintype "passive"))
      (node (ref "CN4") (pin "3") (pinfunction "3_3") (pintype "passive"))
      (node (ref "L9") (pin "2") (pintype "passive"))
      (node (ref "R41") (pin "1") (pinfunction "1_1") (pintype "passive"))
      (node (ref "R42") (pin "1") (pinfunction "1_1") (pintype "passive"))
      (node (ref "R43") (pin "1") (pinfunction "1_1") (pintype "passive"))
      (node (ref "U3") (pin "2") (pinfunction "OUT_2") (pintype "passive"))
    )
    (net (code "42") (name "5V0") (class "Default")
      (node (ref "C14") (pin "2") (pinfunction "2_2") (pintype "passive"))
      (node (ref "C26") (pin "2") (pinfunction "2_2") (pintype "passive"))
      (node (ref "L1") (pin "1") (pintype "passive"))
      (node (ref "L2") (pin "1") (pintype "passive"))
      (node (ref "L3") (pin "1") (pintype "passive"))
      (node (ref "L4") (pin "1") (pintype "passive"))
      (node (ref "L7") (pin "1") (pintype "passive"))
      (node (ref "L8") (pin "1") (pintype "passive"))
      (node (ref "U4") (pin "5") (pinfunction "V_IN_5") (pintype "power_in"))
      (node (ref "U6") (pin "6") (pinfunction "V_IN_6") (pintype "power_in"))
    )
    (net (code "43") (name "AGND") (class "Default")
      (node (ref "C1") (pin "1") (pinfunction "1_1") (pintype "passive"))
      (node (ref "C11") (pin "2") (pinfunction "2_2") (pintype "passive"))
      (node (ref "C12") (pin "2") (pinfunction "2_2") (pintype "passive"))
      (node (ref "C13") (pin "2") (pinfunction "2_2") (pintype "passive"))
      (node (ref "C15") (pin "1") (pinfunction "1_1") (pintype "passive"))
      (node (ref "C17") (pin "1") (pinfunction "1_1") (pintype "passive"))
      (node (ref "C20") (pin "2") (pinfunction "2_2") (pintype "passive"))
      (node (ref "C24") (pin "2") (pinfunction "2_2") (pintype "passive"))
      (node (ref "C5") (pin "1") (pinfunction "1_1") (pintype "passive"))
      (node (ref "CN2") (pin "8") (pinfunction "8_8") (pintype "passive"))
      (node (ref "E1") (pin "2") (pinfunction "C_2") (pintype "passive"))
      (node (ref "E1") (pin "4") (pinfunction "SW_4") (pintype "passive"))
      (node (ref "E2") (pin "2") (pinfunction "C_2") (pintype "passive"))
      (node (ref "E2") (pin "4") (pinfunction "SW_4") (pintype "passive"))
      (node (ref "L6") (pin "1") (pintype "passive"))
      (node (ref "SW1") (pin "1") (pintype "passive"))
      (node (ref "SW2") (pin "1") (pintype "passive"))
      (node (ref "SW3") (pin "1") (pintype "passive"))
      (node (ref "SW4") (pin "1") (pintype "passive"))
      (node (ref "SW5") (pin "1") (pintype "passive"))
    )
    (net (code "44") (name "AVDD") (class "Default")
      (node (ref "C13") (pin "1") (pinfunction "1_1") (pintype "passive"))
      (node (ref "C24") (pin "1") (pinfunction "1_1") (pintype "passive"))
      (node (ref "L5") (pin "1") (pintype "passive"))
      (node (ref "R1") (pin "2") (pinfunction "2_2") (pintype "passive"))
      (node (ref "R11") (pin "2") (pinfunction "2_2") (pintype "passive"))
      (node (ref "R15") (pin "1") (pinfunction "1_1") (pintype "passive"))
      (node (ref "R2") (pin "1") (pinfunction "1_1") (pintype "passive"))
      (node (ref "R24") (pin "2") (pinfunction "2_2") (pintype "passive"))
      (node (ref "R6") (pin "2") (pinfunction "2_2") (pintype "passive"))
    )
    (net (code "45") (name "GND") (class "Default")
      (node (ref "C10") (pin "2") (pinfunction "2_2") (pintype "passive"))
      (node (ref "C14") (pin "1") (pinfunction "1_1") (pintype "passive"))
      (node (ref "C16") (pin "1") (pinfunction "1_1") (pintype "passive"))
      (node (ref "C2") (pin "2") (pinfunction "2_2") (pintype "passive"))
      (node (ref "C22") (pin "1") (pinfunction "1_1") (pintype "passive"))
      (node (ref "C23") (pin "1") (pinfunction "1_1") (pintype "passive"))
      (node (ref "C25") (pin "1") (pinfunction "1_1") (pintype "passive"))
      (node (ref "C26") (pin "1") (pinfunction "1_1") (pintype "passive"))
      (node (ref "C27") (pin "1") (pinfunction "1_1") (pintype "passive"))
      (node (ref "C28") (pin "1") (pinfunction "1_1") (pintype "passive"))
      (node (ref "C29") (pin "1") (pinfunction "1_1") (pintype "passive"))
      (node (ref "C3") (pin "2") (pinfunction "2_2") (pintype "passive"))
      (node (ref "C30") (pin "1") (pinfunction "1_1") (pintype "passive"))
      (node (ref "C31") (pin "2") (pinfunction "2_2") (pintype "passive"))
      (node (ref "C32") (pin "1") (pinfunction "1_1") (pintype "passive"))
      (node (ref "C33") (pin "1") (pinfunction "1_1") (pintype "passive"))
      (node (ref "C34") (pin "1") (pinfunction "1_1") (pintype "passive"))
      (node (ref "C35") (pin "1") (pinfunction "1_1") (pintype "passive"))
      (node (ref "C36") (pin "2") (pinfunction "2_2") (pintype "passive"))
      (node (ref "C37") (pin "1") (pinfunction "1_1") (pintype "passive"))
      (node (ref "C4") (pin "2") (pinfunction "2_2") (pintype "passive"))
      (node (ref "C6") (pin "2") (pinfunction "2_2") (pintype "passive"))
      (node (ref "C7") (pin "2") (pinfunction "2_2") (pintype "passive"))
      (node (ref "C8") (pin "1") (pinfunction "1_1") (pintype "passive"))
      (node (ref "C9") (pin "2") (pinfunction "2_2") (pintype "passive"))
      (node (ref "CN1") (pin "1") (pinfunction "1_1") (pintype "passive"))
      (node (ref "CN1") (pin "13") (pinfunction "13_13") (pintype "passive"))
      (node (ref "CN1") (pin "14") (pinfunction "14_14") (pintype "passive"))
      (node (ref "CN1") (pin "16") (pinfunction "16_16") (pintype "passive"))
      (node (ref "CN1") (pin "18") (pinfunction "18_18") (pintype "passive"))
      (node (ref "CN1") (pin "19") (pinfunction "19_19") (pintype "passive"))
      (node (ref "CN1") (pin "20") (pinfunction "20_20") (pintype "passive"))
      (node (ref "CN1") (pin "25") (pinfunction "25_25") (pintype "passive"))
      (node (ref "CN1") (pin "7") (pinfunction "7_7") (pintype "passive"))
      (node (ref "CN3") (pin "3") (pinfunction "3_3") (pintype "passive"))
      (node (ref "CN4") (pin "10") (pinfunction "10_10") (pintype "passive"))
      (node (ref "CN4") (pin "13") (pinfunction "13_13") (pintype "passive"))
      (node (ref "CN4") (pin "16") (pinfunction "16_16") (pintype "passive"))
      (node (ref "CN4") (pin "19") (pinfunction "19_19") (pintype "passive"))
      (node (ref "CN4") (pin "22") (pinfunction "22_22") (pintype "passive"))
      (node (ref "CN4") (pin "25") (pinfunction "25_25") (pintype "passive"))
      (node (ref "CN4") (pin "30") (pinfunction "30_30") (pintype "passive"))
      (node (ref "CN4") (pin "36") (pinfunction "36_36") (pintype "passive"))
      (node (ref "CN4") (pin "37") (pinfunction "37_37") (pintype "passive"))
      (node (ref "CN4") (pin "7") (pinfunction "7_7") (pintype "passive"))
      (node (ref "L6") (pin "2") (pintype "passive"))
      (node (ref "R20") (pin "2") (pinfunction "2_2") (pintype "passive"))
      (node (ref "R23") (pin "1") (pinfunction "1_1") (pintype "passive"))
      (node (ref "R26") (pin "1") (pinfunction "1_1") (pintype "passive"))
      (node (ref "R29") (pin "1") (pinfunction "1_1") (pintype "passive"))
      (node (ref "R32") (pin "1") (pinfunction "1_1") (pintype "passive"))
      (node (ref "R35") (pin "1") (pinfunction "1_1") (pintype "passive"))
      (node (ref "R36") (pin "1") (pinfunction "1_1") (pintype "passive"))
      (node (ref "R37") (pin "1") (pinfunction "1_1") (pintype "passive"))
      (node (ref "R44") (pin "2") (pinfunction "2_2") (pintype "passive"))
      (node (ref "R45") (pin "2") (pinfunction "2_2") (pintype "passive"))
      (node (ref "R46") (pin "2") (pinfunction "2_2") (pintype "passive"))
      (node (ref "U1") (pin "2") (pinfunction "GND_2") (pintype "power_in"))
      (node (ref "U2") (pin "2") (pinfunction "GND_2") (pintype "power_in"))
      (node (ref "U3") (pin "1") (pinfunction "GND_1") (pintype "passive"))
      (node (ref "U4") (pin "2") (pinfunction "GND_2") (pintype "power_in"))
      (node (ref "U5") (pin "3") (pinfunction "A_3") (pintype "passive"))
      (node (ref "U6") (pin "3") (pinfunction "GND_3") (pintype "power_in"))
      (node (ref "U7") (pin "1") (pinfunction "GND_1") (pintype "power_in"))
      (node (ref "Z1") (pin "2") (pinfunction "K_2") (pintype "passive"))
    )
    (net (code "46") (name "KEYS_VDD") (class "Default")
      (node (ref "C12") (pin "1") (pinfunction "1_1") (pintype "passive"))
      (node (ref "CN2") (pin "1") (pinfunction "1_1") (pintype "passive"))
      (node (ref "L5") (pin "2") (pintype "passive"))
    )
    (net (code "47") (name "Net-(D1-A)") (class "Default")
      (node (ref "C18") (pin "2") (pinfunction "2_2") (pintype "passive"))
      (node (ref "C19") (pin "2") (pinfunction "2_2") (pintype "passive"))
      (node (ref "D1") (pin "1") (pinfunction "A_1") (pintype "passive"))
      (node (ref "L7") (pin "2") (pintype "passive"))
      (node (ref "U4") (pin "1") (pinfunction "SW_1") (pintype "passive"))
    )
    (net (code "48") (name "Net-(D2-A)") (class "Default")
      (node (ref "C22") (pin "2") (pinfunction "2_2") (pintype "passive"))
      (node (ref "D2") (pin "1") (pinfunction "A_1") (pintype "passive"))
      (node (ref "R27") (pin "1") (pinfunction "1_1") (pintype "passive"))
    )
    (net (code "49") (name "Net-(D2-A+K)") (class "Default")
      (node (ref "C18") (pin "1") (pinfunction "1_1") (pintype "passive"))
      (node (ref "D2") (pin "3") (pinfunction "A+K_3") (pintype "passive"))
    )
    (net (code "50") (name "Net-(D2-K)") (class "Default")
      (node (ref "D2") (pin "2") (pinfunction "K_2") (pintype "passive"))
      (node (ref "R20") (pin "1") (pinfunction "1_1") (pintype "passive"))
    )
    (net (code "51") (name "Net-(D3-A+K)") (class "Default")
      (node (ref "C19") (pin "1") (pinfunction "1_1") (pintype "passive"))
      (node (ref "D3") (pin "3") (pinfunction "A+K_3") (pintype "passive"))
    )
    (net (code "52") (name "Net-(D3-K)") (class "Default")
      (node (ref "C23") (pin "2") (pinfunction "2_2") (pintype "passive"))
      (node (ref "D3") (pin "2") (pinfunction "K_2") (pintype "passive"))
      (node (ref "R28") (pin "1") (pinfunction "1_1") (pintype "passive"))
    )
    (net (code "53") (name "Net-(D4-A)") (class "Default")
      (node (ref "D4") (pin "1") (pinfunction "A_1") (pintype "passive"))
      (node (ref "L8") (pin "2") (pintype "passive"))
      (node (ref "U6") (pin "4") (pinfunction "SW_4") (pintype "passive"))
    )
    (net (code "54") (name "Net-(E1-SW-Pad5)") (class "Default")
      (node (ref "E1") (pin "5") (pinfunction "SW_5") (pintype "passive"))
      (node (ref "R5") (pin "2") (pinfunction "2_2") (pintype "passive"))
    )
    (net (code "55") (name "Net-(E2-SW-Pad5)") (class "Default")
      (node (ref "E2") (pin "5") (pinfunction "SW_5") (pintype "passive"))
      (node (ref "R16") (pin "2") (pinfunction "2_2") (pintype "passive"))
    )
    (net (code "56") (name "Net-(R3-Pad1)") (class "Default")
      (node (ref "R3") (pin "1") (pinfunction "1_1") (pintype "passive"))
      (node (ref "SW1") (pin "3") (pintype "passive"))
    )
    (net (code "57") (name "Net-(R4-Pad1)") (class "Default")
      (node (ref "R4") (pin "1") (pinfunction "1_1") (pintype "passive"))
      (node (ref "SW2") (pin "3") (pintype "passive"))
    )
    (net (code "58") (name "Net-(R17-Pad1)") (class "Default")
      (node (ref "R17") (pin "1") (pinfunction "1_1") (pintype "passive"))
      (node (ref "SW3") (pin "3") (pintype "passive"))
    )
    (net (code "59") (name "Net-(R18-Pad1)") (class "Default")
      (node (ref "R18") (pin "1") (pinfunction "1_1") (pintype "passive"))
      (node (ref "SW4") (pin "3") (pintype "passive"))
    )
    (net (code "60") (name "Net-(R19-Pad1)") (class "Default")
      (node (ref "R19") (pin "1") (pinfunction "1_1") (pintype "passive"))
      (node (ref "SW5") (pin "3") (pintype "passive"))
    )
    (net (code "61") (name "Net-(R21-Pad1)") (class "Default")
      (node (ref "R21") (pin "1") (pinfunction "1_1") (pintype "passive"))
      (node (ref "R22") (pin "2") (pinfunction "2_2") (pintype "passive"))
    )
    (net (code "62") (name "Net-(R30-Pad1)") (class "Default")
      (node (ref "R30") (pin "1") (pinfunction "1_1") (pintype "passive"))
      (node (ref "R31") (pin "2") (pinfunction "2_2") (pintype "passive"))
    )
    (net (code "63") (name "Net-(R33-Pad1)") (class "Default")
      (node (ref "R33") (pin "1") (pinfunction "1_1") (pintype "passive"))
      (node (ref "R34") (pin "1") (pinfunction "1_1") (pintype "passive"))
    )
    (net (code "64") (name "Net-(U1-EN)") (class "Default")
      (node (ref "C3") (pin "1") (pinfunction "1_1") (pintype "passive"))
      (node (ref "L2") (pin "2") (pintype "passive"))
      (node (ref "U1") (pin "1") (pinfunction "IN_1") (pintype "power_in"))
      (node (ref "U1") (pin "3") (pinfunction "EN_3") (pintype "input"))
    )
    (net (code "65") (name "Net-(U2-EN)") (class "Default")
      (node (ref "C4") (pin "1") (pinfunction "1_1") (pintype "passive"))
      (node (ref "L3") (pin "2") (pintype "passive"))
      (node (ref "U2") (pin "1") (pinfunction "IN_1") (pintype "power_in"))
      (node (ref "U2") (pin "3") (pinfunction "EN_3") (pintype "input"))
    )
    (net (code "66") (name "Net-(U3-IN)") (class "Default")
      (node (ref "C2") (pin "1") (pinfunction "1_1") (pintype "passive"))
      (node (ref "L1") (pin "2") (pintype "passive"))
      (node (ref "U3") (pin "3") (pinfunction "IN_3") (pintype "passive"))
    )
    (net (code "67") (name "Net-(U4-EN)") (class "Default")
      (node (ref "C16") (pin "2") (pinfunction "2_2") (pintype "passive"))
      (node (ref "R10") (pin "1") (pinfunction "1_1") (pintype "passive"))
      (node (ref "U4") (pin "4") (pinfunction "EN_4") (pintype "input"))
    )
    (net (code "68") (name "Net-(U4-FB)") (class "Default")
      (node (ref "C21") (pin "2") (pinfunction "2_2") (pintype "passive"))
      (node (ref "R22") (pin "1") (pinfunction "1_1") (pintype "passive"))
      (node (ref "R23") (pin "2") (pinfunction "2_2") (pintype "passive"))
      (node (ref "U4") (pin "3") (pinfunction "FB_3") (pintype "passive"))
    )
    (net (code "69") (name "Net-(U5-REF)") (class "Default")
      (node (ref "R29") (pin "2") (pinfunction "2_2") (pintype "passive"))
      (node (ref "R33") (pin "2") (pinfunction "2_2") (pintype "passive"))
      (node (ref "U5") (pin "2") (pinfunction "REF_2") (pintype "input"))
    )
    (net (code "70") (name "Net-(U6-COMP)") (class "Default")
      (node (ref "C27") (pin "2") (pinfunction "2_2") (pintype "passive"))
      (node (ref "U6") (pin "2") (pinfunction "COMP_2") (pintype "passive"))
    )
    (net (code "71") (name "Net-(U6-CTRL)") (class "Default")
      (node (ref "R25") (pin "1") (pinfunction "1_1") (pintype "passive"))
      (node (ref "R26") (pin "2") (pinfunction "2_2") (pintype "passive"))
      (node (ref "U6") (pin "5") (pinfunction "CTRL_5") (pintype "input"))
    )
    (net (code "72") (name "Net-(U7-EN)") (class "Default")
      (node (ref "C33") (pin "2") (pinfunction "2_2") (pintype "passive"))
      (node (ref "R38") (pin "2") (pinfunction "2_2") (pintype "passive"))
      (node (ref "U7") (pin "7") (pinfunction "VREF2_7") (pintype "power_in"))
      (node (ref "U7") (pin "8") (pinfunction "EN_8") (pintype "input"))
    )
    (net (code "73") (name "TP_VDD") (class "Default")
      (node (ref "C36") (pin "1") (pinfunction "1_1") (pintype "passive"))
      (node (ref "CN3") (pin "2") (pinfunction "2_2") (pintype "passive"))
      (node (ref "L9") (pin "1") (pintype "passive"))
      (node (ref "R13") (pin "2") (pinfunction "2_2") (pintype "passive"))
      (node (ref "R14") (pin "2") (pinfunction "2_2") (pintype "passive"))
      (node (ref "R38") (pin "1") (pinfunction "1_1") (pintype "passive"))
      (node (ref "R39") (pin "1") (pinfunction "1_1") (pintype "passive"))
      (node (ref "R40") (pin "1") (pinfunction "1_1") (pintype "passive"))
    )
    (net (code "74") (name "unconnected-(CN4-Pad4)") (class "Default")
      (node (ref "CN4") (pin "4") (pinfunction "4_4") (pintype "passive+no_connect"))
    )
    (net (code "75") (name "unconnected-(CN4-Pad23)") (class "Default")
      (node (ref "CN4") (pin "23") (pinfunction "23_23") (pintype "passive+no_connect"))
    )
    (net (code "76") (name "unconnected-(CN4-Pad24)") (class "Default")
      (node (ref "CN4") (pin "24") (pinfunction "24_24") (pintype "passive+no_connect"))
    )
    (net (code "77") (name "unconnected-(CN4-Pad26)") (class "Default")
      (node (ref "CN4") (pin "26") (pinfunction "26_26") (pintype "passive+no_connect"))
    )
    (net (code "78") (name "unconnected-(CN4-Pad27)") (class "Default")
      (node (ref "CN4") (pin "27") (pinfunction "27_27") (pintype "passive+no_connect"))
    )
    (net (code "79") (name "unconnected-(SW1-Pad2)") (class "Default")
      (node (ref "SW1") (pin "2") (pintype "passive"))
    )
    (net (code "80") (name "unconnected-(SW1-Pad4)") (class "Default")
      (node (ref "SW1") (pin "4") (pintype "passive"))
    )
    (net (code "81") (name "unconnected-(SW2-Pad2)") (class "Default")
      (node (ref "SW2") (pin "2") (pintype "passive"))
    )
    (net (code "82") (name "unconnected-(SW2-Pad4)") (class "Default")
      (node (ref "SW2") (pin "4") (pintype "passive"))
    )
    (net (code "83") (name "unconnected-(SW3-Pad2)") (class "Default")
      (node (ref "SW3") (pin "2") (pintype "passive"))
    )
    (net (code "84") (name "unconnected-(SW3-Pad4)") (class "Default")
      (node (ref "SW3") (pin "4") (pintype "passive"))
    )
    (net (code "85") (name "unconnected-(SW4-Pad2)") (class "Default")
      (node (ref "SW4") (pin "2") (pintype "passive"))
    )
    (net (code "86") (name "unconnected-(SW4-Pad4)") (class "Default")
      (node (ref "SW4") (pin "4") (pintype "passive"))
    )
    (net (code "87") (name "unconnected-(SW5-Pad2)") (class "Default")
      (node (ref "SW5") (pin "2") (pintype "passive"))
    )
    (net (code "88") (name "unconnected-(SW5-Pad4)") (class "Default")
      (node (ref "SW5") (pin "4") (pintype "passive"))
    )
  )
)
